# Stepper_control.net
KiCad netlist of a schematic drawn in Altium Designer
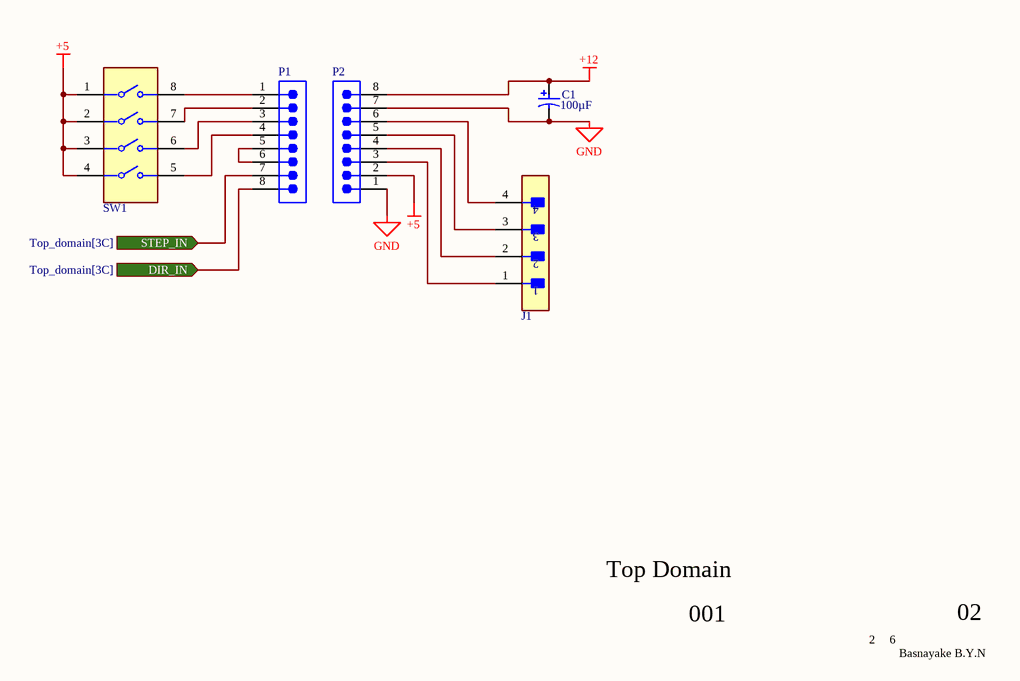
[diagram p0: Stepper_control.SchDoc]

(export (version "E")
  (design (tool "Eeschema 10.0.6"))
  (components
    (comp (ref "C1")
      (value "EEEFK1E101XP")
      (footprint "PNSC-FK-V-D8_V")
      (fields (field (name "CAPACITANCE") "100µF") (field (name "MANUFACTURER") "Panasonic"))
      (libsource (lib "Altium Content Vault") (part "CAP-P-2"))
    )
    (comp (ref "J1")
      (value "B4B-XH-A(LF)(SN)")
      (footprint "FP-B4B-XH-A_LF_SN-MFG")
      (description "CONN HEADER VERT 4POS 2.5MM")
      (libsource (lib "Altium Content Vault") (part "299a8cea1bdcbc3624fe62c390fa72c"))
    )
    (comp (ref "P1")
      (value "61300811121")
      (footprint "61300811121")
      (libsource (lib "Altium Content Vault") (part "Header_Male_1R_08P"))
    )
    (comp (ref "P2")
      (value "61300811121")
      (footprint "61300811121")
      (libsource (lib "Altium Content Vault") (part "Header_Male_1R_08P"))
    )
    (comp (ref "SW1")
      (value "1825360-3")
      (footprint "FP-1825360-3-MFG")
      (description "SWITCH SLIDE DIP SPST 100MA 24V")
      (libsource (lib "Altium Content Vault") (part "8a6f13ad003845d0737bd9d25158ffb"))
    )
  )
  (nets
    (net (code "1") (name "+5") (class "Default")
      (node (ref "P2") (pin "2") (pinfunction "2_2") (pintype "passive"))
      (node (ref "SW1") (pin "1") (pinfunction "1_1") (pintype "passive"))
      (node (ref "SW1") (pin "2") (pinfunction "2_2") (pintype "passive"))
      (node (ref "SW1") (pin "3") (pinfunction "3_3") (pintype "passive"))
      (node (ref "SW1") (pin "4") (pinfunction "4_4") (pintype "passive"))
    )
    (net (code "2") (name "+12") (class "Default")
      (node (ref "C1") (pin "1") (pinfunction "1_1") (pintype "passive"))
      (node (ref "P2") (pin "8") (pinfunction "8_8") (pintype "passive"))
    )
    (net (code "3") (name "/DIR_IN") (class "Default")
      (node (ref "P1") (pin "8") (pinfunction "8_8") (pintype "passive"))
    )
    (net (code "4") (name "/STEP_IN") (class "Default")
      (node (ref "P1") (pin "7") (pinfunction "7_7") (pintype "passive"))
    )
    (net (code "5") (name "GND") (class "Default")
      (node (ref "C1") (pin "2") (pinfunction "2_2") (pintype "passive"))
      (node (ref "P2") (pin "1") (pinfunction "1_1") (pintype "passive"))
      (node (ref "P2") (pin "7") (pinfunction "7_7") (pintype "passive"))
    )
    (net (code "6") (name "Net-(J1-Pad1)") (class "Default")
      (node (ref "J1") (pin "1") (pinfunction "1_1") (pintype "passive"))
      (node (ref "P2") (pin "3") (pinfunction "3_3") (pintype "passive"))
    )
    (net (code "7") (name "Net-(J1-Pad2)") (class "Default")
      (node (ref "J1") (pin "2") (pinfunction "2_2") (pintype "passive"))
      (node (ref "P2") (pin "4") (pinfunction "4_4") (pintype "passive"))
    )
    (net (code "8") (name "Net-(J1-Pad3)") (class "Default")
      (node (ref "J1") (pin "3") (pinfunction "3_3") (pintype "passive"))
      (node (ref "P2") (pin "5") (pinfunction "5_5") (pintype "passive"))
    )
    (net (code "9") (name "Net-(J1-Pad4)") (class "Default")
      (node (ref "J1") (pin "4") (pinfunction "4_4") (pintype "passive"))
      (node (ref "P2") (pin "6") (pinfunction "6_6") (pintype "passive"))
    )
    (net (code "10") (name "Net-(P1-Pad1)") (class "Default")
      (node (ref "P1") (pin "1") (pinfunction "1_1") (pintype "passive"))
      (node (ref "SW1") (pin "8") (pinfunction "8_8") (pintype "passive"))
    )
    (net (code "11") (name "Net-(P1-Pad2)") (class "Default")
      (node (ref "P1") (pin "2") (pinfunction "2_2") (pintype "passive"))
      (node (ref "SW1") (pin "7") (pinfunction "7_7") (pintype "passive"))
    )
    (net (code "12") (name "Net-(P1-Pad3)") (class "Default")
      (node (ref "P1") (pin "3") (pinfunction "3_3") (pintype "passive"))
      (node (ref "SW1") (pin "6") (pinfunction "6_6") (pintype "passive"))
    )
    (net (code "13") (name "Net-(P1-Pad4)") (class "Default")
      (node (ref "P1") (pin "4") (pinfunction "4_4") (pintype "passive"))
      (node (ref "SW1") (pin "5") (pinfunction "5_5") (pintype "passive"))
    )
    (net (code "14") (name "Net-(P1-Pad5)") (class "Default")
      (node (ref "P1") (pin "5") (pinfunction "5_5") (pintype "passive"))
      (node (ref "P1") (pin "6") (pinfunction "6_6") (pintype "passive"))
    )
  )
)
